# crosstalk-3.net
KiCad netlist of a schematic drawn in Altium Designer
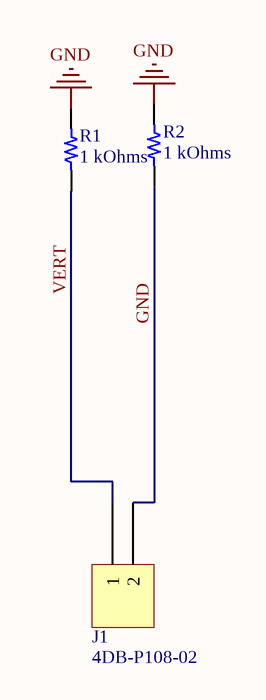
[diagram p0: crosstalk-3.SchDoc]

(export (version "E")
  (design (tool "Eeschema 10.0.6"))
  (components
    (comp (ref "J1")
      (value "4DB-P108-02")
      (footprint "TE 4DB-P108-02")
      (description "CONN BARRIER STRIP 2CIRC 0.325\"")
      (fields (field (name "MANUFACTURER") "TE Connectivity AMP Connectors"))
      (libsource (lib "Celestial Altium Library - altium_library") (part "2 Pin"))
    )
    (comp (ref "R1")
      (value "1 kOhms")
      (footprint "RES 0603_1608")
      (description "RES SMD 1K OHM 0.1% 1/16W 0603")
      (fields
        (field (name "PART NUMBER") "CPF0603B1K0E")
        (field (name "MANUFACTURER") "TE Connectivity Passive Product")
      )
      (libsource (lib "Celestial Altium Library - altium_library") (part "Resistor"))
    )
    (comp (ref "R2")
      (value "1 kOhms")
      (footprint "RES 0603_1608")
      (description "RES SMD 1K OHM 0.1% 1/16W 0603")
      (fields
        (field (name "PART NUMBER") "CPF0603B1K0E")
        (field (name "MANUFACTURER") "TE Connectivity Passive Product")
      )
      (libsource (lib "Celestial Altium Library - altium_library") (part "Resistor"))
    )
  )
  (nets
    (net (code "1") (name "/VERT") (class "Default")
      (node (ref "J1") (pin "1") (pinfunction "1_1") (pintype "passive"))
      (node (ref "R1") (pin "1") (pinfunction "1_1") (pintype "passive"))
    )
    (net (code "2") (name "GND") (class "Default")
      (node (ref "J1") (pin "2") (pinfunction "2_2") (pintype "passive"))
      (node (ref "R1") (pin "2") (pinfunction "2_2") (pintype "passive"))
      (node (ref "R2") (pin "1") (pinfunction "1_1") (pintype "passive"))
      (node (ref "R2") (pin "2") (pinfunction "2_2") (pintype "passive"))
    )
  )
)
